# PROC051C_HD_Connector.net
KiCad netlist of a schematic drawn in Altium Designer
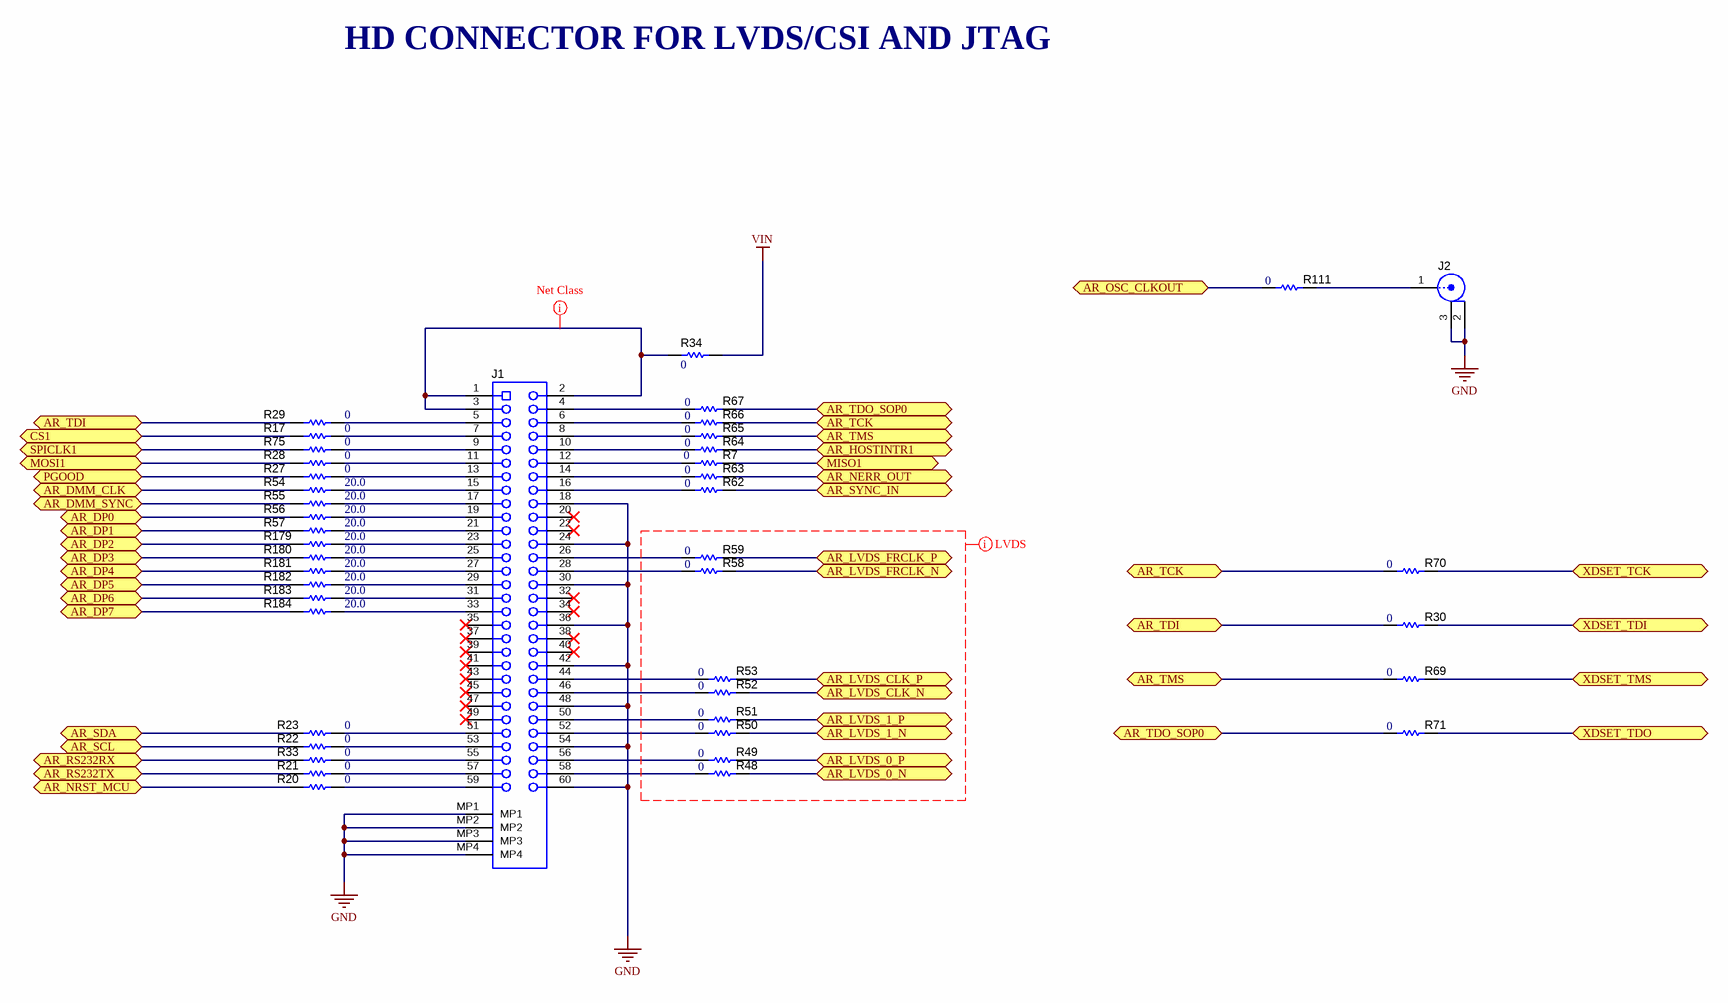
[diagram p0: PROC051C_HD Connector.SchDoc]

(export (version "E")
  (design (tool "Eeschema 10.0.6"))
  (components
    (comp (ref "J1")
      (value "QSH-030-01-L-D-A")
      (footprint "Samtec_QSH-030-01-X-D-A")
      (description "Receptacle, 0.5 mm, 30x2, Gold, TH")
      (fields (field (name "MANUFACTURER") "Samtec") (field (name "PUBLISHER") "Texas Instruments"))
      (libsource (lib "Altium Vault - TI") (part "CMP-0075524-1"))
    )
    (comp (ref "J2")
      (value "128-0711-201")
      (footprint "Johnson_128-0711-201")
      (description "UMC Straight Jack Receptacle, 50 Ohm, Gold, SMT")
      (fields
        (field (name "MANUFACTURER") "Cinch Connectivity")
        (field (name "PUBLISHER") "Texas Instruments")
      )
      (libsource (lib "Altium Vault - TI") (part "CMP-0055788-1"))
    )
    (comp (ref "R7")
      (value "CRCW02010000Z0ED")
      (footprint "0201_Silk")
      (description "RES, 0, 5%, 0.05 W, 0201")
      (fields (field (name "MANUFACTURER") "Vishay-Dale") (field (name "VALUEDISPLAYED") "0"))
      (libsource (lib "Altium Vault - TI") (part "Resistor"))
    )
    (comp (ref "R17")
      (value "CRCW02010000Z0ED")
      (footprint "0201_Silk")
      (description "RES, 0, 5%, 0.05 W, 0201")
      (fields (field (name "MANUFACTURER") "Vishay-Dale") (field (name "VALUEDISPLAYED") "0"))
      (libsource (lib "Altium Vault - TI") (part "Resistor"))
    )
    (comp (ref "R20")
      (value "CRCW02010000Z0ED")
      (footprint "0201_Silk")
      (description "RES, 0, 5%, 0.05 W, 0201")
      (fields (field (name "MANUFACTURER") "Vishay-Dale") (field (name "VALUEDISPLAYED") "0"))
      (libsource (lib "Altium Vault - TI") (part "Resistor"))
    )
    (comp (ref "R21")
      (value "CRCW02010000Z0ED")
      (footprint "0201_Silk")
      (description "RES, 0, 5%, 0.05 W, 0201")
      (fields (field (name "MANUFACTURER") "Vishay-Dale") (field (name "VALUEDISPLAYED") "0"))
      (libsource (lib "Altium Vault - TI") (part "Resistor"))
    )
    (comp (ref "R22")
      (value "CRCW02010000Z0ED")
      (footprint "0201_Silk")
      (description "RES, 0, 5%, 0.05 W, 0201")
      (fields (field (name "MANUFACTURER") "Vishay-Dale") (field (name "VALUEDISPLAYED") "0"))
      (libsource (lib "Altium Vault - TI") (part "Resistor"))
    )
    (comp (ref "R23")
      (value "CRCW02010000Z0ED")
      (footprint "0201_Silk")
      (description "RES, 0, 5%, 0.05 W, 0201")
      (fields (field (name "MANUFACTURER") "Vishay-Dale") (field (name "VALUEDISPLAYED") "0"))
      (libsource (lib "Altium Vault - TI") (part "Resistor"))
    )
    (comp (ref "R27")
      (value "CRCW02010000Z0ED")
      (footprint "0201_Silk")
      (description "RES, 0, 5%, 0.05 W, 0201")
      (fields (field (name "MANUFACTURER") "Vishay-Dale") (field (name "VALUEDISPLAYED") "0"))
      (libsource (lib "Altium Vault - TI") (part "Resistor"))
    )
    (comp (ref "R28")
      (value "CRCW02010000Z0ED")
      (footprint "0201_Silk")
      (description "RES, 0, 5%, 0.05 W, 0201")
      (fields (field (name "MANUFACTURER") "Vishay-Dale") (field (name "VALUEDISPLAYED") "0"))
      (libsource (lib "Altium Vault - TI") (part "Resistor"))
    )
    (comp (ref "R29")
      (value "CRCW02010000Z0ED")
      (footprint "0201_Silk")
      (description "RES, 0, 5%, 0.05 W, 0201")
      (fields (field (name "MANUFACTURER") "Vishay-Dale") (field (name "VALUEDISPLAYED") "0"))
      (libsource (lib "Altium Vault - TI") (part "Resistor"))
    )
    (comp (ref "R30")
      (value "CRCW02010000Z0ED")
      (footprint "0201_Silk")
      (description "RES, 0, 5%, 0.05 W, 0201")
      (fields (field (name "MANUFACTURER") "Vishay-Dale") (field (name "VALUEDISPLAYED") "0"))
      (libsource (lib "Altium Vault - TI") (part "Resistor"))
    )
    (comp (ref "R33")
      (value "CRCW02010000Z0ED")
      (footprint "0201_Silk")
      (description "RES, 0, 5%, 0.05 W, 0201")
      (fields (field (name "MANUFACTURER") "Vishay-Dale") (field (name "VALUEDISPLAYED") "0"))
      (libsource (lib "Altium Vault - TI") (part "Resistor"))
    )
    (comp (ref "R34")
      (value "CRCW20100000Z0EF")
      (footprint "2010")
      (description "RES, 0, 5%, 0.75 W, AEC-Q200 Grade 0, 2010")
      (fields (field (name "MANUFACTURER") "Vishay-Dale") (field (name "VALUEDISPLAYED") "0"))
      (libsource (lib "Altium Vault - TI") (part "Resistor"))
    )
    (comp (ref "R48")
      (value "CRCW02010000Z0ED")
      (footprint "0201_Silk")
      (description "RES, 0, 5%, 0.05 W, 0201")
      (fields (field (name "MANUFACTURER") "Vishay-Dale") (field (name "VALUEDISPLAYED") "0"))
      (libsource (lib "Altium Vault - TI") (part "Resistor"))
    )
    (comp (ref "R49")
      (value "CRCW02010000Z0ED")
      (footprint "0201_Silk")
      (description "RES, 0, 5%, 0.05 W, 0201")
      (fields (field (name "MANUFACTURER") "Vishay-Dale") (field (name "VALUEDISPLAYED") "0"))
      (libsource (lib "Altium Vault - TI") (part "Resistor"))
    )
    (comp (ref "R50")
      (value "CRCW02010000Z0ED")
      (footprint "0201_Silk")
      (description "RES, 0, 5%, 0.05 W, 0201")
      (fields (field (name "MANUFACTURER") "Vishay-Dale") (field (name "VALUEDISPLAYED") "0"))
      (libsource (lib "Altium Vault - TI") (part "Resistor"))
    )
    (comp (ref "R51")
      (value "CRCW02010000Z0ED")
      (footprint "0201_Silk")
      (description "RES, 0, 5%, 0.05 W, 0201")
      (fields (field (name "MANUFACTURER") "Vishay-Dale") (field (name "VALUEDISPLAYED") "0"))
      (libsource (lib "Altium Vault - TI") (part "Resistor"))
    )
    (comp (ref "R52")
      (value "CRCW02010000Z0ED")
      (footprint "0201_Silk")
      (description "RES, 0, 5%, 0.05 W, 0201")
      (fields (field (name "MANUFACTURER") "Vishay-Dale") (field (name "VALUEDISPLAYED") "0"))
      (libsource (lib "Altium Vault - TI") (part "Resistor"))
    )
    (comp (ref "R53")
      (value "CRCW02010000Z0ED")
      (footprint "0201_Silk")
      (description "RES, 0, 5%, 0.05 W, 0201")
      (fields (field (name "MANUFACTURER") "Vishay-Dale") (field (name "VALUEDISPLAYED") "0"))
      (libsource (lib "Altium Vault - TI") (part "Resistor"))
    )
    (comp (ref "R54")
      (value "CRCW020120R0FNED")
      (footprint "0201_033")
      (description "RES, 20.0, 1%, 0.05 W, 0201")
      (fields (field (name "MANUFACTURER") "Vishay-Dale") (field (name "VALUEDISPLAYED") "20.0"))
      (libsource (lib "Altium Vault - TI") (part "Resistor"))
    )
    (comp (ref "R55")
      (value "CRCW020120R0FNED")
      (footprint "0201_033")
      (description "RES, 20.0, 1%, 0.05 W, 0201")
      (fields (field (name "MANUFACTURER") "Vishay-Dale") (field (name "VALUEDISPLAYED") "20.0"))
      (libsource (lib "Altium Vault - TI") (part "Resistor"))
    )
    (comp (ref "R56")
      (value "CRCW020120R0FNED")
      (footprint "0201_033")
      (description "RES, 20.0, 1%, 0.05 W, 0201")
      (fields (field (name "MANUFACTURER") "Vishay-Dale") (field (name "VALUEDISPLAYED") "20.0"))
      (libsource (lib "Altium Vault - TI") (part "Resistor"))
    )
    (comp (ref "R57")
      (value "CRCW020120R0FNED")
      (footprint "0201_033")
      (description "RES, 20.0, 1%, 0.05 W, 0201")
      (fields (field (name "MANUFACTURER") "Vishay-Dale") (field (name "VALUEDISPLAYED") "20.0"))
      (libsource (lib "Altium Vault - TI") (part "Resistor"))
    )
    (comp (ref "R58")
      (value "CRCW02010000Z0ED")
      (footprint "0201_Silk")
      (description "RES, 0, 5%, 0.05 W, 0201")
      (fields (field (name "MANUFACTURER") "Vishay-Dale") (field (name "VALUEDISPLAYED") "0"))
      (libsource (lib "Altium Vault - TI") (part "Resistor"))
    )
    (comp (ref "R59")
      (value "CRCW02010000Z0ED")
      (footprint "0201_Silk")
      (description "RES, 0, 5%, 0.05 W, 0201")
      (fields (field (name "MANUFACTURER") "Vishay-Dale") (field (name "VALUEDISPLAYED") "0"))
      (libsource (lib "Altium Vault - TI") (part "Resistor"))
    )
    (comp (ref "R62")
      (value "CRCW02010000Z0ED")
      (footprint "0201_Silk")
      (description "RES, 0, 5%, 0.05 W, 0201")
      (fields (field (name "MANUFACTURER") "Vishay-Dale") (field (name "VALUEDISPLAYED") "0"))
      (libsource (lib "Altium Vault - TI") (part "Resistor"))
    )
    (comp (ref "R63")
      (value "CRCW02010000Z0ED")
      (footprint "0201_Silk")
      (description "RES, 0, 5%, 0.05 W, 0201")
      (fields (field (name "MANUFACTURER") "Vishay-Dale") (field (name "VALUEDISPLAYED") "0"))
      (libsource (lib "Altium Vault - TI") (part "Resistor"))
    )
    (comp (ref "R64")
      (value "CRCW02010000Z0ED")
      (footprint "0201_Silk")
      (description "RES, 0, 5%, 0.05 W, 0201")
      (fields (field (name "MANUFACTURER") "Vishay-Dale") (field (name "VALUEDISPLAYED") "0"))
      (libsource (lib "Altium Vault - TI") (part "Resistor"))
    )
    (comp (ref "R65")
      (value "CRCW02010000Z0ED")
      (footprint "0201_Silk")
      (description "RES, 0, 5%, 0.05 W, 0201")
      (fields (field (name "MANUFACTURER") "Vishay-Dale") (field (name "VALUEDISPLAYED") "0"))
      (libsource (lib "Altium Vault - TI") (part "Resistor"))
    )
    (comp (ref "R66")
      (value "CRCW02010000Z0ED")
      (footprint "0201_Silk")
      (description "RES, 0, 5%, 0.05 W, 0201")
      (fields (field (name "MANUFACTURER") "Vishay-Dale") (field (name "VALUEDISPLAYED") "0"))
      (libsource (lib "Altium Vault - TI") (part "Resistor"))
    )
    (comp (ref "R67")
      (value "CRCW02010000Z0ED")
      (footprint "0201_Silk")
      (description "RES, 0, 5%, 0.05 W, 0201")
      (fields (field (name "MANUFACTURER") "Vishay-Dale") (field (name "VALUEDISPLAYED") "0"))
      (libsource (lib "Altium Vault - TI") (part "Resistor"))
    )
    (comp (ref "R69")
      (value "CRCW02010000Z0ED")
      (footprint "0201_Silk")
      (description "RES, 0, 5%, 0.05 W, 0201")
      (fields (field (name "MANUFACTURER") "Vishay-Dale") (field (name "VALUEDISPLAYED") "0"))
      (libsource (lib "Altium Vault - TI") (part "Resistor"))
    )
    (comp (ref "R70")
      (value "CRCW02010000Z0ED")
      (footprint "0201_Silk")
      (description "RES, 0, 5%, 0.05 W, 0201")
      (fields (field (name "MANUFACTURER") "Vishay-Dale") (field (name "VALUEDISPLAYED") "0"))
      (libsource (lib "Altium Vault - TI") (part "Resistor"))
    )
    (comp (ref "R71")
      (value "CRCW02010000Z0ED")
      (footprint "0201_Silk")
      (description "RES, 0, 5%, 0.05 W, 0201")
      (fields (field (name "MANUFACTURER") "Vishay-Dale") (field (name "VALUEDISPLAYED") "0"))
      (libsource (lib "Altium Vault - TI") (part "Resistor"))
    )
    (comp (ref "R75")
      (value "CRCW02010000Z0ED")
      (footprint "0201_Silk")
      (description "RES, 0, 5%, 0.05 W, 0201")
      (fields (field (name "MANUFACTURER") "Vishay-Dale") (field (name "VALUEDISPLAYED") "0"))
      (libsource (lib "Altium Vault - TI") (part "Resistor"))
    )
    (comp (ref "R111")
      (value "CRCW02010000Z0ED")
      (footprint "0201_Silk")
      (description "RES, 0, 5%, 0.05 W, 0201")
      (fields (field (name "MANUFACTURER") "Vishay-Dale") (field (name "VALUEDISPLAYED") "0"))
      (libsource (lib "Altium Vault - TI") (part "Resistor"))
    )
    (comp (ref "R179")
      (value "CRCW020120R0FNED")
      (footprint "0201_033")
      (description "RES, 20.0, 1%, 0.05 W, 0201")
      (fields (field (name "MANUFACTURER") "Vishay-Dale") (field (name "VALUEDISPLAYED") "20.0"))
      (libsource (lib "Altium Vault - TI") (part "Resistor"))
    )
    (comp (ref "R180")
      (value "CRCW020120R0FNED")
      (footprint "0201_033")
      (description "RES, 20.0, 1%, 0.05 W, 0201")
      (fields (field (name "MANUFACTURER") "Vishay-Dale") (field (name "VALUEDISPLAYED") "20.0"))
      (libsource (lib "Altium Vault - TI") (part "Resistor"))
    )
    (comp (ref "R181")
      (value "CRCW020120R0FNED")
      (footprint "0201_033")
      (description "RES, 20.0, 1%, 0.05 W, 0201")
      (fields (field (name "MANUFACTURER") "Vishay-Dale") (field (name "VALUEDISPLAYED") "20.0"))
      (libsource (lib "Altium Vault - TI") (part "Resistor"))
    )
    (comp (ref "R182")
      (value "CRCW020120R0FNED")
      (footprint "0201_033")
      (description "RES, 20.0, 1%, 0.05 W, 0201")
      (fields (field (name "MANUFACTURER") "Vishay-Dale") (field (name "VALUEDISPLAYED") "20.0"))
      (libsource (lib "Altium Vault - TI") (part "Resistor"))
    )
    (comp (ref "R183")
      (value "CRCW020120R0FNED")
      (footprint "0201_033")
      (description "RES, 20.0, 1%, 0.05 W, 0201")
      (fields (field (name "MANUFACTURER") "Vishay-Dale") (field (name "VALUEDISPLAYED") "20.0"))
      (libsource (lib "Altium Vault - TI") (part "Resistor"))
    )
    (comp (ref "R184")
      (value "CRCW020120R0FNED")
      (footprint "0201_033")
      (description "RES, 20.0, 1%, 0.05 W, 0201")
      (fields (field (name "MANUFACTURER") "Vishay-Dale") (field (name "VALUEDISPLAYED") "20.0"))
      (libsource (lib "Altium Vault - TI") (part "Resistor"))
    )
  )
  (nets
    (net (code "1") (name "/AR_DMM_CLK") (class "Default")
      (node (ref "R54") (pin "1") (pinfunction "1_1") (pintype "passive"))
    )
    (net (code "2") (name "/AR_DMM_SYNC") (class "Default")
      (node (ref "R55") (pin "1") (pinfunction "1_1") (pintype "passive"))
    )
    (net (code "3") (name "/AR_DP0") (class "Default")
      (node (ref "R56") (pin "1") (pinfunction "1_1") (pintype "passive"))
    )
    (net (code "4") (name "/AR_DP1") (class "Default")
      (node (ref "R57") (pin "1") (pinfunction "1_1") (pintype "passive"))
    )
    (net (code "5") (name "/AR_DP2") (class "Default")
      (node (ref "R179") (pin "1") (pinfunction "1_1") (pintype "passive"))
    )
    (net (code "6") (name "/AR_DP3") (class "Default")
      (node (ref "R180") (pin "1") (pinfunction "1_1") (pintype "passive"))
    )
    (net (code "7") (name "/AR_DP4") (class "Default")
      (node (ref "R181") (pin "1") (pinfunction "1_1") (pintype "passive"))
    )
    (net (code "8") (name "/AR_DP5") (class "Default")
      (node (ref "R182") (pin "1") (pinfunction "1_1") (pintype "passive"))
    )
    (net (code "9") (name "/AR_DP6") (class "Default")
      (node (ref "R183") (pin "1") (pinfunction "1_1") (pintype "passive"))
    )
    (net (code "10") (name "/AR_DP7") (class "Default")
      (node (ref "R184") (pin "1") (pinfunction "1_1") (pintype "passive"))
    )
    (net (code "11") (name "/AR_HOSTINTR1") (class "Default")
      (node (ref "R64") (pin "2") (pinfunction "2_2") (pintype "passive"))
    )
    (net (code "12") (name "/AR_LVDS_0_N") (class "Default")
      (node (ref "R48") (pin "2") (pinfunction "2_2") (pintype "passive"))
    )
    (net (code "13") (name "/AR_LVDS_0_P") (class "Default")
      (node (ref "R49") (pin "2") (pinfunction "2_2") (pintype "passive"))
    )
    (net (code "14") (name "/AR_LVDS_1_N") (class "Default")
      (node (ref "R50") (pin "2") (pinfunction "2_2") (pintype "passive"))
    )
    (net (code "15") (name "/AR_LVDS_1_P") (class "Default")
      (node (ref "R51") (pin "2") (pinfunction "2_2") (pintype "passive"))
    )
    (net (code "16") (name "/AR_LVDS_CLK_N") (class "Default")
      (node (ref "R52") (pin "2") (pinfunction "2_2") (pintype "passive"))
    )
    (net (code "17") (name "/AR_LVDS_CLK_P") (class "Default")
      (node (ref "R53") (pin "2") (pinfunction "2_2") (pintype "passive"))
    )
    (net (code "18") (name "/AR_LVDS_FRCLK_N") (class "Default")
      (node (ref "R58") (pin "2") (pinfunction "2_2") (pintype "passive"))
    )
    (net (code "19") (name "/AR_LVDS_FRCLK_P") (class "Default")
      (node (ref "R59") (pin "2") (pinfunction "2_2") (pintype "passive"))
    )
    (net (code "20") (name "/AR_NERR_OUT") (class "Default")
      (node (ref "R63") (pin "2") (pinfunction "2_2") (pintype "passive"))
    )
    (net (code "21") (name "/AR_NRST_MCU") (class "Default")
      (node (ref "R20") (pin "1") (pinfunction "1_1") (pintype "passive"))
    )
    (net (code "22") (name "/AR_OSC_CLKOUT") (class "Default")
      (node (ref "R111") (pin "1") (pinfunction "1_1") (pintype "passive"))
    )
    (net (code "23") (name "/AR_RS232RX") (class "Default")
      (node (ref "R33") (pin "1") (pinfunction "1_1") (pintype "passive"))
    )
    (net (code "24") (name "/AR_RS232TX") (class "Default")
      (node (ref "R21") (pin "1") (pinfunction "1_1") (pintype "passive"))
    )
    (net (code "25") (name "/AR_SCL") (class "Default")
      (node (ref "R22") (pin "1") (pinfunction "1_1") (pintype "passive"))
    )
    (net (code "26") (name "/AR_SDA") (class "Default")
      (node (ref "R23") (pin "1") (pinfunction "1_1") (pintype "passive"))
    )
    (net (code "27") (name "/AR_SYNC_IN") (class "Default")
      (node (ref "R62") (pin "2") (pinfunction "2_2") (pintype "passive"))
    )
    (net (code "28") (name "/AR_TCK") (class "Default")
      (node (ref "R66") (pin "2") (pinfunction "2_2") (pintype "passive"))
      (node (ref "R70") (pin "1") (pinfunction "1_1") (pintype "passive"))
    )
    (net (code "29") (name "/AR_TDI") (class "Default")
      (node (ref "R29") (pin "1") (pinfunction "1_1") (pintype "passive"))
      (node (ref "R30") (pin "1") (pinfunction "1_1") (pintype "passive"))
    )
    (net (code "30") (name "/AR_TDO_SOP0") (class "Default")
      (node (ref "R67") (pin "2") (pinfunction "2_2") (pintype "passive"))
      (node (ref "R71") (pin "1") (pinfunction "1_1") (pintype "passive"))
    )
    (net (code "31") (name "/AR_TMS") (class "Default")
      (node (ref "R65") (pin "2") (pinfunction "2_2") (pintype "passive"))
      (node (ref "R69") (pin "1") (pinfunction "1_1") (pintype "passive"))
    )
    (net (code "32") (name "/CS1") (class "Default")
      (node (ref "R17") (pin "1") (pinfunction "1_1") (pintype "passive"))
    )
    (net (code "33") (name "/MISO1") (class "Default")
      (node (ref "R7") (pin "2") (pinfunction "2_2") (pintype "passive"))
    )
    (net (code "34") (name "/MOSI1") (class "Default")
      (node (ref "R28") (pin "1") (pinfunction "1_1") (pintype "passive"))
    )
    (net (code "35") (name "/PGOOD") (class "Default")
      (node (ref "R27") (pin "1") (pinfunction "1_1") (pintype "passive"))
    )
    (net (code "36") (name "/SPICLK1") (class "Default")
      (node (ref "R75") (pin "1") (pinfunction "1_1") (pintype "passive"))
    )
    (net (code "37") (name "/XDSET_TCK") (class "Default")
      (node (ref "R70") (pin "2") (pinfunction "2_2") (pintype "passive"))
    )
    (net (code "38") (name "/XDSET_TDI") (class "Default")
      (node (ref "R30") (pin "2") (pinfunction "2_2") (pintype "passive"))
    )
    (net (code "39") (name "/XDSET_TDO") (class "Default")
      (node (ref "R71") (pin "2") (pinfunction "2_2") (pintype "passive"))
    )
    (net (code "40") (name "/XDSET_TMS") (class "Default")
      (node (ref "R69") (pin "2") (pinfunction "2_2") (pintype "passive"))
    )
    (net (code "41") (name "GND") (class "Default")
      (node (ref "J1") (pin "18") (pinfunction "18_18") (pintype "passive"))
      (node (ref "J1") (pin "24") (pinfunction "24_24") (pintype "passive"))
      (node (ref "J1") (pin "30") (pinfunction "30_30") (pintype "passive"))
      (node (ref "J1") (pin "36") (pinfunction "36_36") (pintype "passive"))
      (node (ref "J1") (pin "42") (pinfunction "42_42") (pintype "passive"))
      (node (ref "J1") (pin "48") (pinfunction "48_48") (pintype "passive"))
      (node (ref "J1") (pin "54") (pinfunction "54_54") (pintype "passive"))
      (node (ref "J1") (pin "60") (pinfunction "60_60") (pintype "passive"))
      (node (ref "J1") (pin "MP1") (pinfunction "MP1_MP1") (pintype "passive"))
      (node (ref "J1") (pin "MP2") (pinfunction "MP2_MP2") (pintype "passive"))
      (node (ref "J1") (pin "MP3") (pinfunction "MP3_MP3") (pintype "passive"))
      (node (ref "J1") (pin "MP4") (pinfunction "MP4_MP4") (pintype "passive"))
      (node (ref "J2") (pin "2") (pinfunction "2_2") (pintype "passive"))
      (node (ref "J2") (pin "3") (pinfunction "3_3") (pintype "passive"))
    )
    (net (code "42") (name "Net-(J1-Pad1)") (class "Default")
      (node (ref "J1") (pin "1") (pinfunction "1_1") (pintype "passive"))
      (node (ref "J1") (pin "2") (pinfunction "2_2") (pintype "passive"))
      (node (ref "J1") (pin "3") (pinfunction "3_3") (pintype "passive"))
      (node (ref "R34") (pin "1") (pinfunction "1_1") (pintype "passive"))
    )
    (net (code "43") (name "Net-(J1-Pad4)") (class "Default")
      (node (ref "J1") (pin "4") (pinfunction "4_4") (pintype "passive"))
      (node (ref "R67") (pin "1") (pinfunction "1_1") (pintype "passive"))
    )
    (net (code "44") (name "Net-(J1-Pad5)") (class "Default")
      (node (ref "J1") (pin "5") (pinfunction "5_5") (pintype "passive"))
      (node (ref "R29") (pin "2") (pinfunction "2_2") (pintype "passive"))
    )
    (net (code "45") (name "Net-(J1-Pad6)") (class "Default")
      (node (ref "J1") (pin "6") (pinfunction "6_6") (pintype "passive"))
      (node (ref "R66") (pin "1") (pinfunction "1_1") (pintype "passive"))
    )
    (net (code "46") (name "Net-(J1-Pad7)") (class "Default")
      (node (ref "J1") (pin "7") (pinfunction "7_7") (pintype "passive"))
      (node (ref "R17") (pin "2") (pinfunction "2_2") (pintype "passive"))
    )
    (net (code "47") (name "Net-(J1-Pad8)") (class "Default")
      (node (ref "J1") (pin "8") (pinfunction "8_8") (pintype "passive"))
      (node (ref "R65") (pin "1") (pinfunction "1_1") (pintype "passive"))
    )
    (net (code "48") (name "Net-(J1-Pad9)") (class "Default")
      (node (ref "J1") (pin "9") (pinfunction "9_9") (pintype "passive"))
      (node (ref "R75") (pin "2") (pinfunction "2_2") (pintype "passive"))
    )
    (net (code "49") (name "Net-(J1-Pad10)") (class "Default")
      (node (ref "J1") (pin "10") (pinfunction "10_10") (pintype "passive"))
      (node (ref "R64") (pin "1") (pinfunction "1_1") (pintype "passive"))
    )
    (net (code "50") (name "Net-(J1-Pad11)") (class "Default")
      (node (ref "J1") (pin "11") (pinfunction "11_11") (pintype "passive"))
      (node (ref "R28") (pin "2") (pinfunction "2_2") (pintype "passive"))
    )
    (net (code "51") (name "Net-(J1-Pad12)") (class "Default")
      (node (ref "J1") (pin "12") (pinfunction "12_12") (pintype "passive"))
      (node (ref "R7") (pin "1") (pinfunction "1_1") (pintype "passive"))
    )
    (net (code "52") (name "Net-(J1-Pad13)") (class "Default")
      (node (ref "J1") (pin "13") (pinfunction "13_13") (pintype "passive"))
      (node (ref "R27") (pin "2") (pinfunction "2_2") (pintype "passive"))
    )
    (net (code "53") (name "Net-(J1-Pad14)") (class "Default")
      (node (ref "J1") (pin "14") (pinfunction "14_14") (pintype "passive"))
      (node (ref "R63") (pin "1") (pinfunction "1_1") (pintype "passive"))
    )
    (net (code "54") (name "Net-(J1-Pad15)") (class "Default")
      (node (ref "J1") (pin "15") (pinfunction "15_15") (pintype "passive"))
      (node (ref "R54") (pin "2") (pinfunction "2_2") (pintype "passive"))
    )
    (net (code "55") (name "Net-(J1-Pad16)") (class "Default")
      (node (ref "J1") (pin "16") (pinfunction "16_16") (pintype "passive"))
      (node (ref "R62") (pin "1") (pinfunction "1_1") (pintype "passive"))
    )
    (net (code "56") (name "Net-(J1-Pad17)") (class "Default")
      (node (ref "J1") (pin "17") (pinfunction "17_17") (pintype "passive"))
      (node (ref "R55") (pin "2") (pinfunction "2_2") (pintype "passive"))
    )
    (net (code "57") (name "Net-(J1-Pad19)") (class "Default")
      (node (ref "J1") (pin "19") (pinfunction "19_19") (pintype "passive"))
      (node (ref "R56") (pin "2") (pinfunction "2_2") (pintype "passive"))
    )
    (net (code "58") (name "Net-(J1-Pad21)") (class "Default")
      (node (ref "J1") (pin "21") (pinfunction "21_21") (pintype "passive"))
      (node (ref "R57") (pin "2") (pinfunction "2_2") (pintype "passive"))
    )
    (net (code "59") (name "Net-(J1-Pad23)") (class "Default")
      (node (ref "J1") (pin "23") (pinfunction "23_23") (pintype "passive"))
      (node (ref "R179") (pin "2") (pinfunction "2_2") (pintype "passive"))
    )
    (net (code "60") (name "Net-(J1-Pad25)") (class "Default")
      (node (ref "J1") (pin "25") (pinfunction "25_25") (pintype "passive"))
      (node (ref "R180") (pin "2") (pinfunction "2_2") (pintype "passive"))
    )
    (net (code "61") (name "Net-(J1-Pad26)") (class "Default")
      (node (ref "J1") (pin "26") (pinfunction "26_26") (pintype "passive"))
      (node (ref "R59") (pin "1") (pinfunction "1_1") (pintype "passive"))
    )
    (net (code "62") (name "Net-(J1-Pad27)") (class "Default")
      (node (ref "J1") (pin "27") (pinfunction "27_27") (pintype "passive"))
      (node (ref "R181") (pin "2") (pinfunction "2_2") (pintype "passive"))
    )
    (net (code "63") (name "Net-(J1-Pad28)") (class "Default")
      (node (ref "J1") (pin "28") (pinfunction "28_28") (pintype "passive"))
      (node (ref "R58") (pin "1") (pinfunction "1_1") (pintype "passive"))
    )
    (net (code "64") (name "Net-(J1-Pad29)") (class "Default")
      (node (ref "J1") (pin "29") (pinfunction "29_29") (pintype "passive"))
      (node (ref "R182") (pin "2") (pinfunction "2_2") (pintype "passive"))
    )
    (net (code "65") (name "Net-(J1-Pad31)") (class "Default")
      (node (ref "J1") (pin "31") (pinfunction "31_31") (pintype "passive"))
      (node (ref "R183") (pin "2") (pinfunction "2_2") (pintype "passive"))
    )
    (net (code "66") (name "Net-(J1-Pad33)") (class "Default")
      (node (ref "J1") (pin "33") (pinfunction "33_33") (pintype "passive"))
      (node (ref "R184") (pin "2") (pinfunction "2_2") (pintype "passive"))
    )
    (net (code "67") (name "Net-(J1-Pad44)") (class "Default")
      (node (ref "J1") (pin "44") (pinfunction "44_44") (pintype "passive"))
      (node (ref "R53") (pin "1") (pinfunction "1_1") (pintype "passive"))
    )
    (net (code "68") (name "Net-(J1-Pad46)") (class "Default")
      (node (ref "J1") (pin "46") (pinfunction "46_46") (pintype "passive"))
      (node (ref "R52") (pin "1") (pinfunction "1_1") (pintype "passive"))
    )
    (net (code "69") (name "Net-(J1-Pad50)") (class "Default")
      (node (ref "J1") (pin "50") (pinfunction "50_50") (pintype "passive"))
      (node (ref "R51") (pin "1") (pinfunction "1_1") (pintype "passive"))
    )
    (net (code "70") (name "Net-(J1-Pad51)") (class "Default")
      (node (ref "J1") (pin "51") (pinfunction "51_51") (pintype "passive"))
      (node (ref "R23") (pin "2") (pinfunction "2_2") (pintype "passive"))
    )
    (net (code "71") (name "Net-(J1-Pad52)") (class "Default")
      (node (ref "J1") (pin "52") (pinfunction "52_52") (pintype "passive"))
      (node (ref "R50") (pin "1") (pinfunction "1_1") (pintype "passive"))
    )
    (net (code "72") (name "Net-(J1-Pad53)") (class "Default")
      (node (ref "J1") (pin "53") (pinfunction "53_53") (pintype "passive"))
      (node (ref "R22") (pin "2") (pinfunction "2_2") (pintype "passive"))
    )
    (net (code "73") (name "Net-(J1-Pad55)") (class "Default")
      (node (ref "J1") (pin "55") (pinfunction "55_55") (pintype "passive"))
      (node (ref "R33") (pin "2") (pinfunction "2_2") (pintype "passive"))
    )
    (net (code "74") (name "Net-(J1-Pad56)") (class "Default")
      (node (ref "J1") (pin "56") (pinfunction "56_56") (pintype "passive"))
      (node (ref "R49") (pin "1") (pinfunction "1_1") (pintype "passive"))
    )
    (net (code "75") (name "Net-(J1-Pad57)") (class "Default")
      (node (ref "J1") (pin "57") (pinfunction "57_57") (pintype "passive"))
      (node (ref "R21") (pin "2") (pinfunction "2_2") (pintype "passive"))
    )
    (net (code "76") (name "Net-(J1-Pad58)") (class "Default")
      (node (ref "J1") (pin "58") (pinfunction "58_58") (pintype "passive"))
      (node (ref "R48") (pin "1") (pinfunction "1_1") (pintype "passive"))
    )
    (net (code "77") (name "Net-(J1-Pad59)") (class "Default")
      (node (ref "J1") (pin "59") (pinfunction "59_59") (pintype "passive"))
      (node (ref "R20") (pin "2") (pinfunction "2_2") (pintype "passive"))
    )
    (net (code "78") (name "Net-(J2-Pad1)") (class "Default")
      (node (ref "J2") (pin "1") (pinfunction "1_1") (pintype "passive"))
      (node (ref "R111") (pin "2") (pinfunction "2_2") (pintype "passive"))
    )
    (net (code "79") (name "VIN") (class "Default")
      (node (ref "R34") (pin "2") (pinfunction "2_2") (pintype "passive"))
    )
    (net (code "80") (name "unconnected-(J1-Pad20)") (class "Default")
      (node (ref "J1") (pin "20") (pinfunction "20_20") (pintype "passive+no_connect"))
    )
    (net (code "81") (name "unconnected-(J1-Pad22)") (class "Default")
      (node (ref "J1") (pin "22") (pinfunction "22_22") (pintype "passive+no_connect"))
    )
    (net (code "82") (name "unconnected-(J1-Pad32)") (class "Default")
      (node (ref "J1") (pin "32") (pinfunction "32_32") (pintype "passive+no_connect"))
    )
    (net (code "83") (name "unconnected-(J1-Pad34)") (class "Default")
      (node (ref "J1") (pin "34") (pinfunction "34_34") (pintype "passive+no_connect"))
    )
    (net (code "84") (name "unconnected-(J1-Pad35)") (class "Default")
      (node (ref "J1") (pin "35") (pinfunction "35_35") (pintype "passive+no_connect"))
    )
    (net (code "85") (name "unconnected-(J1-Pad37)") (class "Default")
      (node (ref "J1") (pin "37") (pinfunction "37_37") (pintype "passive+no_connect"))
    )
    (net (code "86") (name "unconnected-(J1-Pad38)") (class "Default")
      (node (ref "J1") (pin "38") (pinfunction "38_38") (pintype "passive+no_connect"))
    )
    (net (code "87") (name "unconnected-(J1-Pad39)") (class "Default")
      (node (ref "J1") (pin "39") (pinfunction "39_39") (pintype "passive+no_connect"))
    )
    (net (code "88") (name "unconnected-(J1-Pad40)") (class "Default")
      (node (ref "J1") (pin "40") (pinfunction "40_40") (pintype "passive+no_connect"))
    )
    (net (code "89") (name "unconnected-(J1-Pad41)") (class "Default")
      (node (ref "J1") (pin "41") (pinfunction "41_41") (pintype "passive+no_connect"))
    )
    (net (code "90") (name "unconnected-(J1-Pad43)") (class "Default")
      (node (ref "J1") (pin "43") (pinfunction "43_43") (pintype "passive+no_connect"))
    )
    (net (code "91") (name "unconnected-(J1-Pad45)") (class "Default")
      (node (ref "J1") (pin "45") (pinfunction "45_45") (pintype "passive+no_connect"))
    )
    (net (code "92") (name "unconnected-(J1-Pad47)") (class "Default")
      (node (ref "J1") (pin "47") (pinfunction "47_47") (pintype "passive+no_connect"))
    )
    (net (code "93") (name "unconnected-(J1-Pad49)") (class "Default")
      (node (ref "J1") (pin "49") (pinfunction "49_49") (pintype "passive+no_connect"))
    )
  )
)
